# Receiver_STC12C5608AD.net
KiCad netlist of a schematic drawn in Altium Designer
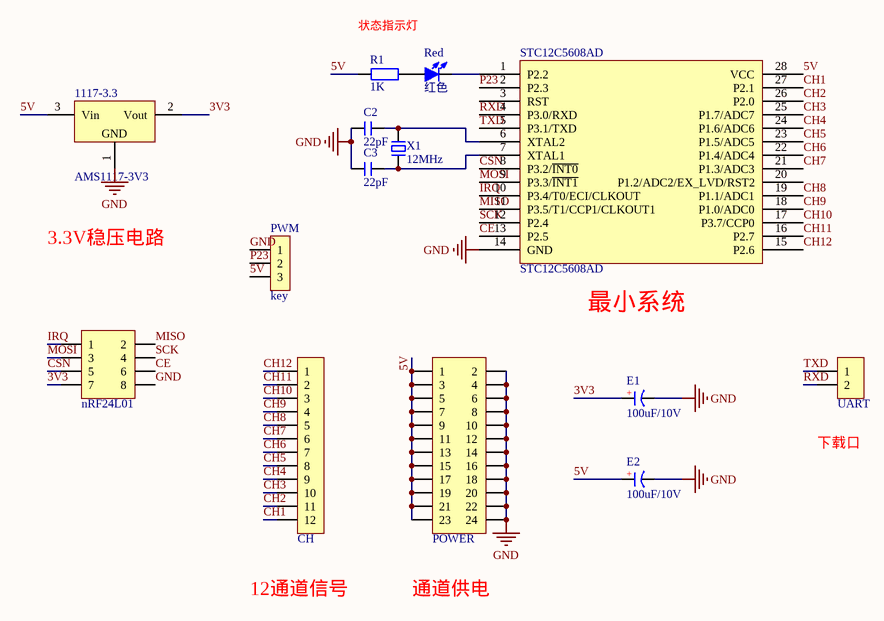
[diagram p0: Receiver_STC12C5608AD.SchDoc]

(export (version "E")
  (design (tool "Eeschema 10.0.6"))
  (components
    (comp (ref "1117-3.3")
      (value "AMS1117-3V3")
      (footprint "SOT223_L")
      (description "三端稳压芯片")
      (fields (field (name "版权归属") "源创客"))
      (libsource (lib "HexapodRobot_STC15W4K48S4") (part "AMS1117"))
    )
    (comp (ref "C2")
      (value "22pF")
      (footprint "C 0603")
      (description "无极性贴片电容")
      (fields (field (name "版权归属") "源创客"))
      (libsource (lib "HexapodRobot_STC15F2K60S2") (part "C"))
    )
    (comp (ref "C3")
      (value "22pF")
      (footprint "C 0603")
      (description "无极性贴片电容")
      (fields (field (name "版权归属") "源创客"))
      (libsource (lib "HexapodRobot_STC15F2K60S2") (part "C"))
    )
    (comp (ref "CH")
      (value "HDR-1X12")
      (footprint "HDR-1X12")
      (description "12P接插件")
      (fields (field (name "版权归属") "源创客"))
      (libsource (lib "Receiver_STC12C5608AD") (part "Header 12"))
    )
    (comp (ref "E1")
      (value "100uF/10V")
      (footprint "CD C(6032)")
      (description "贴片钽电容")
      (fields (field (name "版权归属") "源创客"))
      (libsource (lib "Receiver_STC12C5608AD") (part "C-CD"))
    )
    (comp (ref "E2")
      (value "100uF/10V")
      (footprint "CD C(6032)")
      (description "贴片钽电容")
      (fields (field (name "版权归属") "源创客"))
      (libsource (lib "Receiver_STC12C5608AD") (part "C-CD"))
    )
    (comp (ref "nRF24L01")
      (value "Header 4X2")
      (footprint "HDR-4X2")
      (description "4*2P接插件")
      (fields (field (name "版权归属") "源创客"))
      (libsource (lib "Receiver_STC12C5608AD") (part "Header 4X2"))
    )
    (comp (ref "POWER")
      (value "Header 2X11")
      (footprint "HDR-12X2")
      (description "12*2P接插件")
      (fields (field (name "版权归属") "源创客"))
      (libsource (lib "Receiver_STC12C5608AD") (part "Header 12X2"))
    )
    (comp (ref "PWM")
      (value "key")
      (footprint "HDR-1X3")
      (libsource (lib "Receiver_STC12C5608AD") (part "KEY"))
    )
    (comp (ref "R1")
      (value "1K")
      (footprint "R 0603")
      (description "贴片电阻")
      (fields (field (name "版权归属") "源创客"))
      (libsource (lib "HexapodRobot_STC15F2K60S2") (part "R"))
    )
    (comp (ref "Red")
      (value "红色")
      (footprint "LED 0603R")
      (description "贴片LED")
      (fields (field (name "版权归属") "源创客"))
      (libsource (lib "HexapodRobot_STC15F2K60S2") (part "LED-SMD"))
    )
    (comp (ref "STC12C5608AD")
      (value "STC12C5608AD")
      (footprint "SOP28_N")
      (description "STC带AD单片机")
      (fields (field (name "版权归属") "源创客"))
      (libsource (lib "Receiver_STC12C5608AD") (part "STC12C520xAD-28pin"))
    )
    (comp (ref "UART")
      (value "HDR-1X2")
      (footprint "HDR-1X2")
      (description "2P接插件")
      (fields (field (name "版权归属") "源创客"))
      (libsource (lib "Receiver_STC12C5608AD") (part "Header 2"))
    )
    (comp (ref "X1")
      (value "12MHz")
      (footprint "XTAL-49S DIP")
      (description "2脚晶振")
      (fields (field (name "版权归属") "源创客"))
      (libsource (lib "HexapodRobot_STC15F2K60S2") (part "XTAL-2"))
    )
  )
  (nets
    (net (code "1") (name "/3V3") (class "Default")
      (node (ref "1117-3.3") (pin "2") (pinfunction "Vout_2") (pintype "passive"))
      (node (ref "E1") (pin "1") (pinfunction "A_1") (pintype "passive"))
      (node (ref "nRF24L01") (pin "7") (pinfunction "7_7") (pintype "passive"))
    )
    (net (code "2") (name "/5V") (class "Default")
      (node (ref "1117-3.3") (pin "3") (pinfunction "Vin_3") (pintype "passive"))
      (node (ref "E2") (pin "1") (pinfunction "A_1") (pintype "passive"))
      (node (ref "POWER") (pin "1") (pinfunction "1_1") (pintype "passive"))
      (node (ref "POWER") (pin "11") (pinfunction "11_11") (pintype "passive"))
      (node (ref "POWER") (pin "13") (pinfunction "13_13") (pintype "passive"))
      (node (ref "POWER") (pin "15") (pinfunction "15_15") (pintype "passive"))
      (node (ref "POWER") (pin "17") (pinfunction "17_17") (pintype "passive"))
      (node (ref "POWER") (pin "19") (pinfunction "19_19") (pintype "passive"))
      (node (ref "POWER") (pin "21") (pinfunction "21_21") (pintype "passive"))
      (node (ref "POWER") (pin "23") (pinfunction "23_23") (pintype "passive"))
      (node (ref "POWER") (pin "3") (pinfunction "3_3") (pintype "passive"))
      (node (ref "POWER") (pin "5") (pinfunction "5_5") (pintype "passive"))
      (node (ref "POWER") (pin "7") (pinfunction "7_7") (pintype "passive"))
      (node (ref "POWER") (pin "9") (pinfunction "9_9") (pintype "passive"))
      (node (ref "PWM") (pin "3") (pinfunction "3_3") (pintype "passive"))
      (node (ref "R1") (pin "1") (pinfunction "1_1") (pintype "passive"))
      (node (ref "STC12C5608AD") (pin "28") (pinfunction "VCC_28") (pintype "passive"))
    )
    (net (code "3") (name "/CE") (class "Default")
      (node (ref "STC12C5608AD") (pin "13") (pinfunction "P2.5_13") (pintype "passive"))
      (node (ref "nRF24L01") (pin "6") (pinfunction "6_6") (pintype "passive"))
    )
    (net (code "4") (name "/CH1") (class "Default")
      (node (ref "CH") (pin "12") (pinfunction "12_12") (pintype "passive"))
      (node (ref "STC12C5608AD") (pin "27") (pinfunction "P2.1_27") (pintype "passive"))
    )
    (net (code "5") (name "/CH2") (class "Default")
      (node (ref "CH") (pin "11") (pinfunction "11_11") (pintype "passive"))
      (node (ref "STC12C5608AD") (pin "26") (pinfunction "P2.0_26") (pintype "passive"))
    )
    (net (code "6") (name "/CH3") (class "Default")
      (node (ref "CH") (pin "10") (pinfunction "10_10") (pintype "passive"))
      (node (ref "STC12C5608AD") (pin "25") (pinfunction "P1.7/ADC7_25") (pintype "passive"))
    )
    (net (code "7") (name "/CH4") (class "Default")
      (node (ref "CH") (pin "9") (pinfunction "9_9") (pintype "passive"))
      (node (ref "STC12C5608AD") (pin "24") (pinfunction "P1.6/ADC6_24") (pintype "passive"))
    )
    (net (code "8") (name "/CH5") (class "Default")
      (node (ref "CH") (pin "8") (pinfunction "8_8") (pintype "passive"))
      (node (ref "STC12C5608AD") (pin "23") (pinfunction "P1.5/ADC5_23") (pintype "passive"))
    )
    (net (code "9") (name "/CH6") (class "Default")
      (node (ref "CH") (pin "7") (pinfunction "7_7") (pintype "passive"))
      (node (ref "STC12C5608AD") (pin "22") (pinfunction "P1.4/ADC4_22") (pintype "passive"))
    )
    (net (code "10") (name "/CH7") (class "Default")
      (node (ref "CH") (pin "6") (pinfunction "6_6") (pintype "passive"))
      (node (ref "STC12C5608AD") (pin "21") (pinfunction "P1.3/ADC3_21") (pintype "passive"))
    )
    (net (code "11") (name "/CH8") (class "Default")
      (node (ref "CH") (pin "5") (pinfunction "5_5") (pintype "passive"))
      (node (ref "STC12C5608AD") (pin "19") (pinfunction "P1.1/ADC1_19") (pintype "passive"))
    )
    (net (code "12") (name "/CH9") (class "Default")
      (node (ref "CH") (pin "4") (pinfunction "4_4") (pintype "passive"))
      (node (ref "STC12C5608AD") (pin "18") (pinfunction "P1.0/ADC0_18") (pintype "passive"))
    )
    (net (code "13") (name "/CH10") (class "Default")
      (node (ref "CH") (pin "3") (pinfunction "3_3") (pintype "passive"))
      (node (ref "STC12C5608AD") (pin "17") (pinfunction "P3.7/CCP0_17") (pintype "passive"))
    )
    (net (code "14") (name "/CH11") (class "Default")
      (node (ref "CH") (pin "2") (pinfunction "2_2") (pintype "passive"))
      (node (ref "STC12C5608AD") (pin "16") (pinfunction "P2.7_16") (pintype "passive"))
    )
    (net (code "15") (name "/CH12") (class "Default")
      (node (ref "CH") (pin "1") (pinfunction "1_1") (pintype "passive"))
      (node (ref "STC12C5608AD") (pin "15") (pinfunction "P2.6_15") (pintype "passive"))
    )
    (net (code "16") (name "/CSN") (class "Default")
      (node (ref "STC12C5608AD") (pin "8") (pinfunction "P3.2/~{INT0}_8") (pintype "passive"))
      (node (ref "nRF24L01") (pin "5") (pinfunction "5_5") (pintype "passive"))
    )
    (net (code "17") (name "/IRQ") (class "Default")
      (node (ref "STC12C5608AD") (pin "10") (pinfunction "P3.4/T0/ECI/CLKOUT_10") (pintype "passive"))
      (node (ref "nRF24L01") (pin "1") (pinfunction "1_1") (pintype "passive"))
    )
    (net (code "18") (name "/MISO") (class "Default")
      (node (ref "STC12C5608AD") (pin "11") (pinfunction "P3.5/T1/CCP1/CLKOUT1_11") (pintype "passive"))
      (node (ref "nRF24L01") (pin "2") (pinfunction "2_2") (pintype "passive"))
    )
    (net (code "19") (name "/MOSI") (class "Default")
      (node (ref "STC12C5608AD") (pin "9") (pinfunction "P3.3/~{INT1}_9") (pintype "passive"))
      (node (ref "nRF24L01") (pin "3") (pinfunction "3_3") (pintype "passive"))
    )
    (net (code "20") (name "/P23") (class "Default")
      (node (ref "PWM") (pin "2") (pinfunction "2_2") (pintype "passive"))
      (node (ref "STC12C5608AD") (pin "2") (pinfunction "P2.3_2") (pintype "passive"))
    )
    (net (code "21") (name "/RXD") (class "Default")
      (node (ref "STC12C5608AD") (pin "4") (pinfunction "P3.0/RXD_4") (pintype "passive"))
      (node (ref "UART") (pin "2") (pinfunction "2_2") (pintype "passive"))
    )
    (net (code "22") (name "/SCK") (class "Default")
      (node (ref "STC12C5608AD") (pin "12") (pinfunction "P2.4_12") (pintype "passive"))
      (node (ref "nRF24L01") (pin "4") (pinfunction "4_4") (pintype "passive"))
    )
    (net (code "23") (name "/TXD") (class "Default")
      (node (ref "STC12C5608AD") (pin "5") (pinfunction "P3.1/TXD_5") (pintype "passive"))
      (node (ref "UART") (pin "1") (pinfunction "1_1") (pintype "passive"))
    )
    (net (code "24") (name "GND") (class "Default")
      (node (ref "1117-3.3") (pin "1") (pinfunction "GND_1") (pintype "passive"))
      (node (ref "C2") (pin "1") (pinfunction "1_1") (pintype "passive"))
      (node (ref "C3") (pin "1") (pinfunction "1_1") (pintype "passive"))
      (node (ref "E1") (pin "2") (pinfunction "K_2") (pintype "passive"))
      (node (ref "E2") (pin "2") (pinfunction "K_2") (pintype "passive"))
      (node (ref "POWER") (pin "10") (pinfunction "10_10") (pintype "passive"))
      (node (ref "POWER") (pin "12") (pinfunction "12_12") (pintype "passive"))
      (node (ref "POWER") (pin "14") (pinfunction "14_14") (pintype "passive"))
      (node (ref "POWER") (pin "16") (pinfunction "16_16") (pintype "passive"))
      (node (ref "POWER") (pin "18") (pinfunction "18_18") (pintype "passive"))
      (node (ref "POWER") (pin "2") (pinfunction "2_2") (pintype "passive"))
      (node (ref "POWER") (pin "20") (pinfunction "20_20") (pintype "passive"))
      (node (ref "POWER") (pin "22") (pinfunction "22_22") (pintype "passive"))
      (node (ref "POWER") (pin "24") (pinfunction "24_24") (pintype "passive"))
      (node (ref "POWER") (pin "4") (pinfunction "4_4") (pintype "passive"))
      (node (ref "POWER") (pin "6") (pinfunction "6_6") (pintype "passive"))
      (node (ref "POWER") (pin "8") (pinfunction "8_8") (pintype "passive"))
      (node (ref "PWM") (pin "1") (pinfunction "1_1") (pintype "passive"))
      (node (ref "STC12C5608AD") (pin "14") (pinfunction "GND_14") (pintype "passive"))
      (node (ref "nRF24L01") (pin "8") (pinfunction "8_8") (pintype "passive"))
    )
    (net (code "25") (name "Net-(Red-A)") (class "Default")
      (node (ref "R1") (pin "2") (pinfunction "2_2") (pintype "passive"))
      (node (ref "Red") (pin "1") (pinfunction "A_1") (pintype "passive"))
    )
    (net (code "26") (name "Net-(Red-K)") (class "Default")
      (node (ref "Red") (pin "2") (pinfunction "K_2") (pintype "passive"))
      (node (ref "STC12C5608AD") (pin "1") (pinfunction "P2.2_1") (pintype "passive"))
    )
    (net (code "27") (name "Net-(STC12C5608AD-XTAL1)") (class "Default")
      (node (ref "C3") (pin "2") (pinfunction "2_2") (pintype "passive"))
      (node (ref "STC12C5608AD") (pin "7") (pinfunction "XTAL1_7") (pintype "passive"))
      (node (ref "X1") (pin "1") (pinfunction "1_1") (pintype "passive"))
    )
    (net (code "28") (name "Net-(STC12C5608AD-XTAL2)") (class "Default")
      (node (ref "C2") (pin "2") (pinfunction "2_2") (pintype "passive"))
      (node (ref "STC12C5608AD") (pin "6") (pinfunction "XTAL2_6") (pintype "passive"))
      (node (ref "X1") (pin "2") (pinfunction "2_2") (pintype "passive"))
    )
    (net (code "29") (name "unconnected-(STC12C5608AD-P1.2{slash}ADC2{slash}EX_LVD{slash}RST2-Pad20)") (class "Default")
      (node (ref "STC12C5608AD") (pin "20") (pinfunction "P1.2/ADC2/EX_LVD/RST2_20") (pintype "passive"))
    )
    (net (code "30") (name "unconnected-(STC12C5608AD-RST-Pad3)") (class "Default")
      (node (ref "STC12C5608AD") (pin "3") (pinfunction "RST_3") (pintype "passive"))
    )
  )
)
